# ArduinoInterface_v4_2.net
KiCad netlist of a schematic drawn in EAGLE
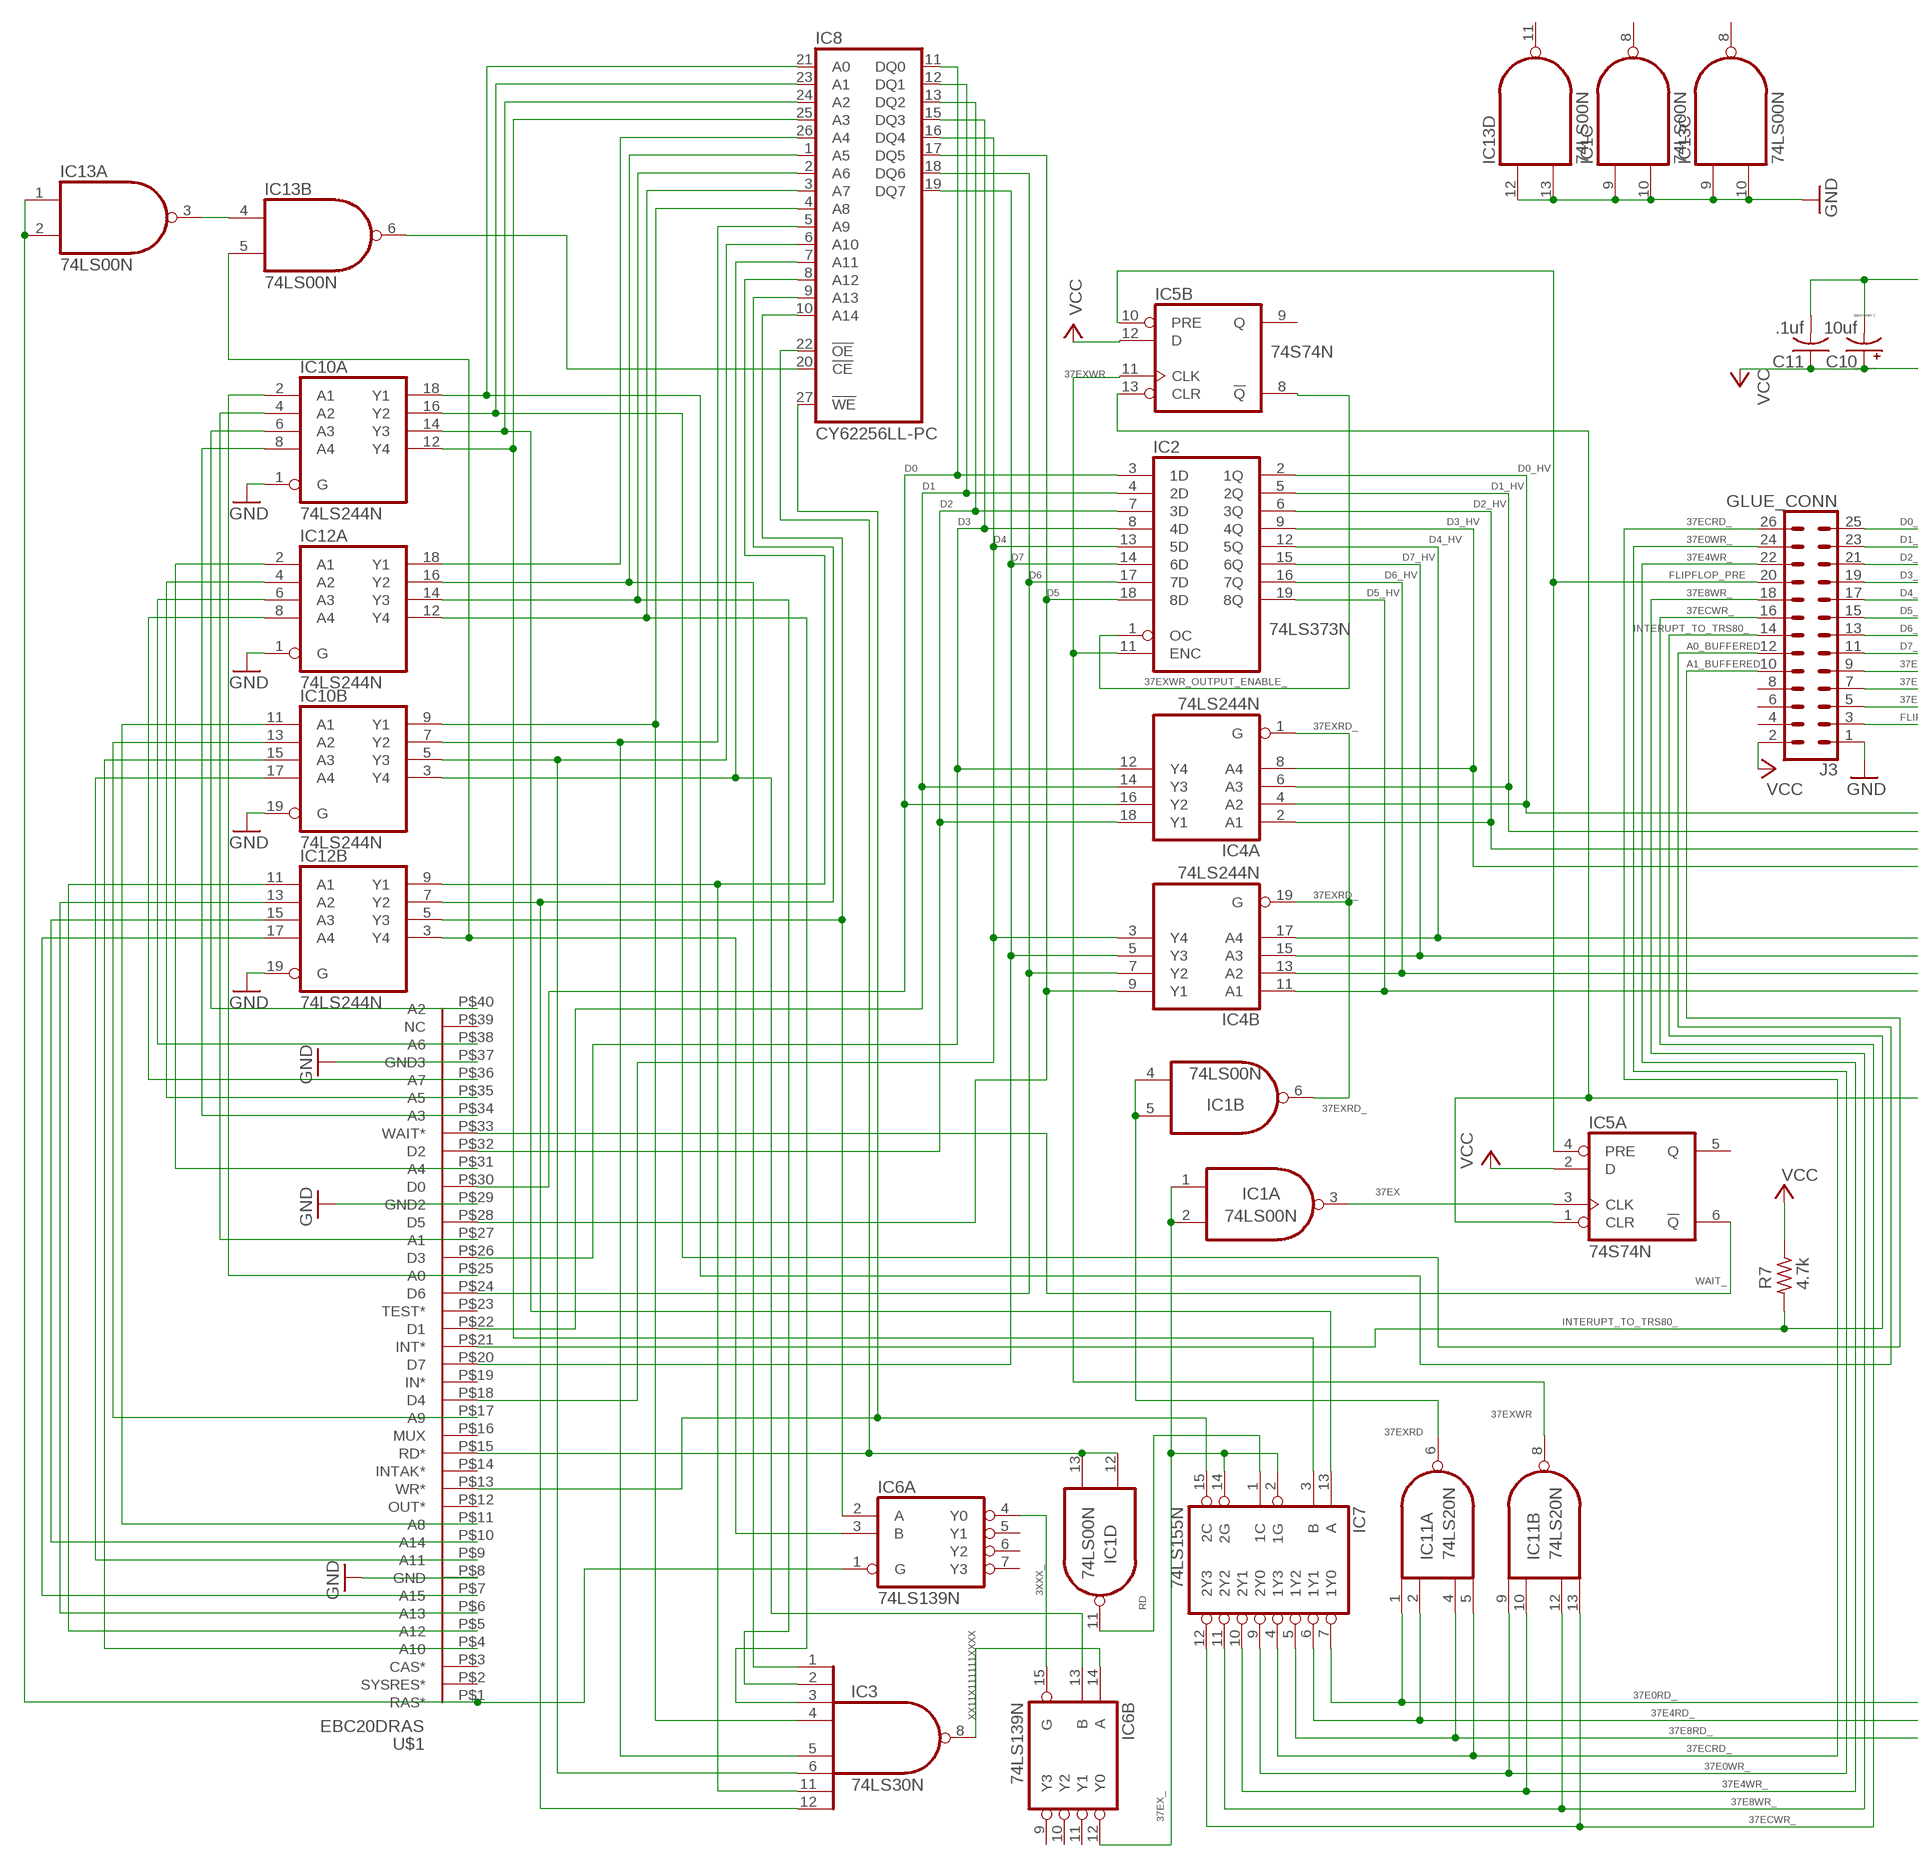
[diagram p0: schematic, sheet 1, part 1 of 2]
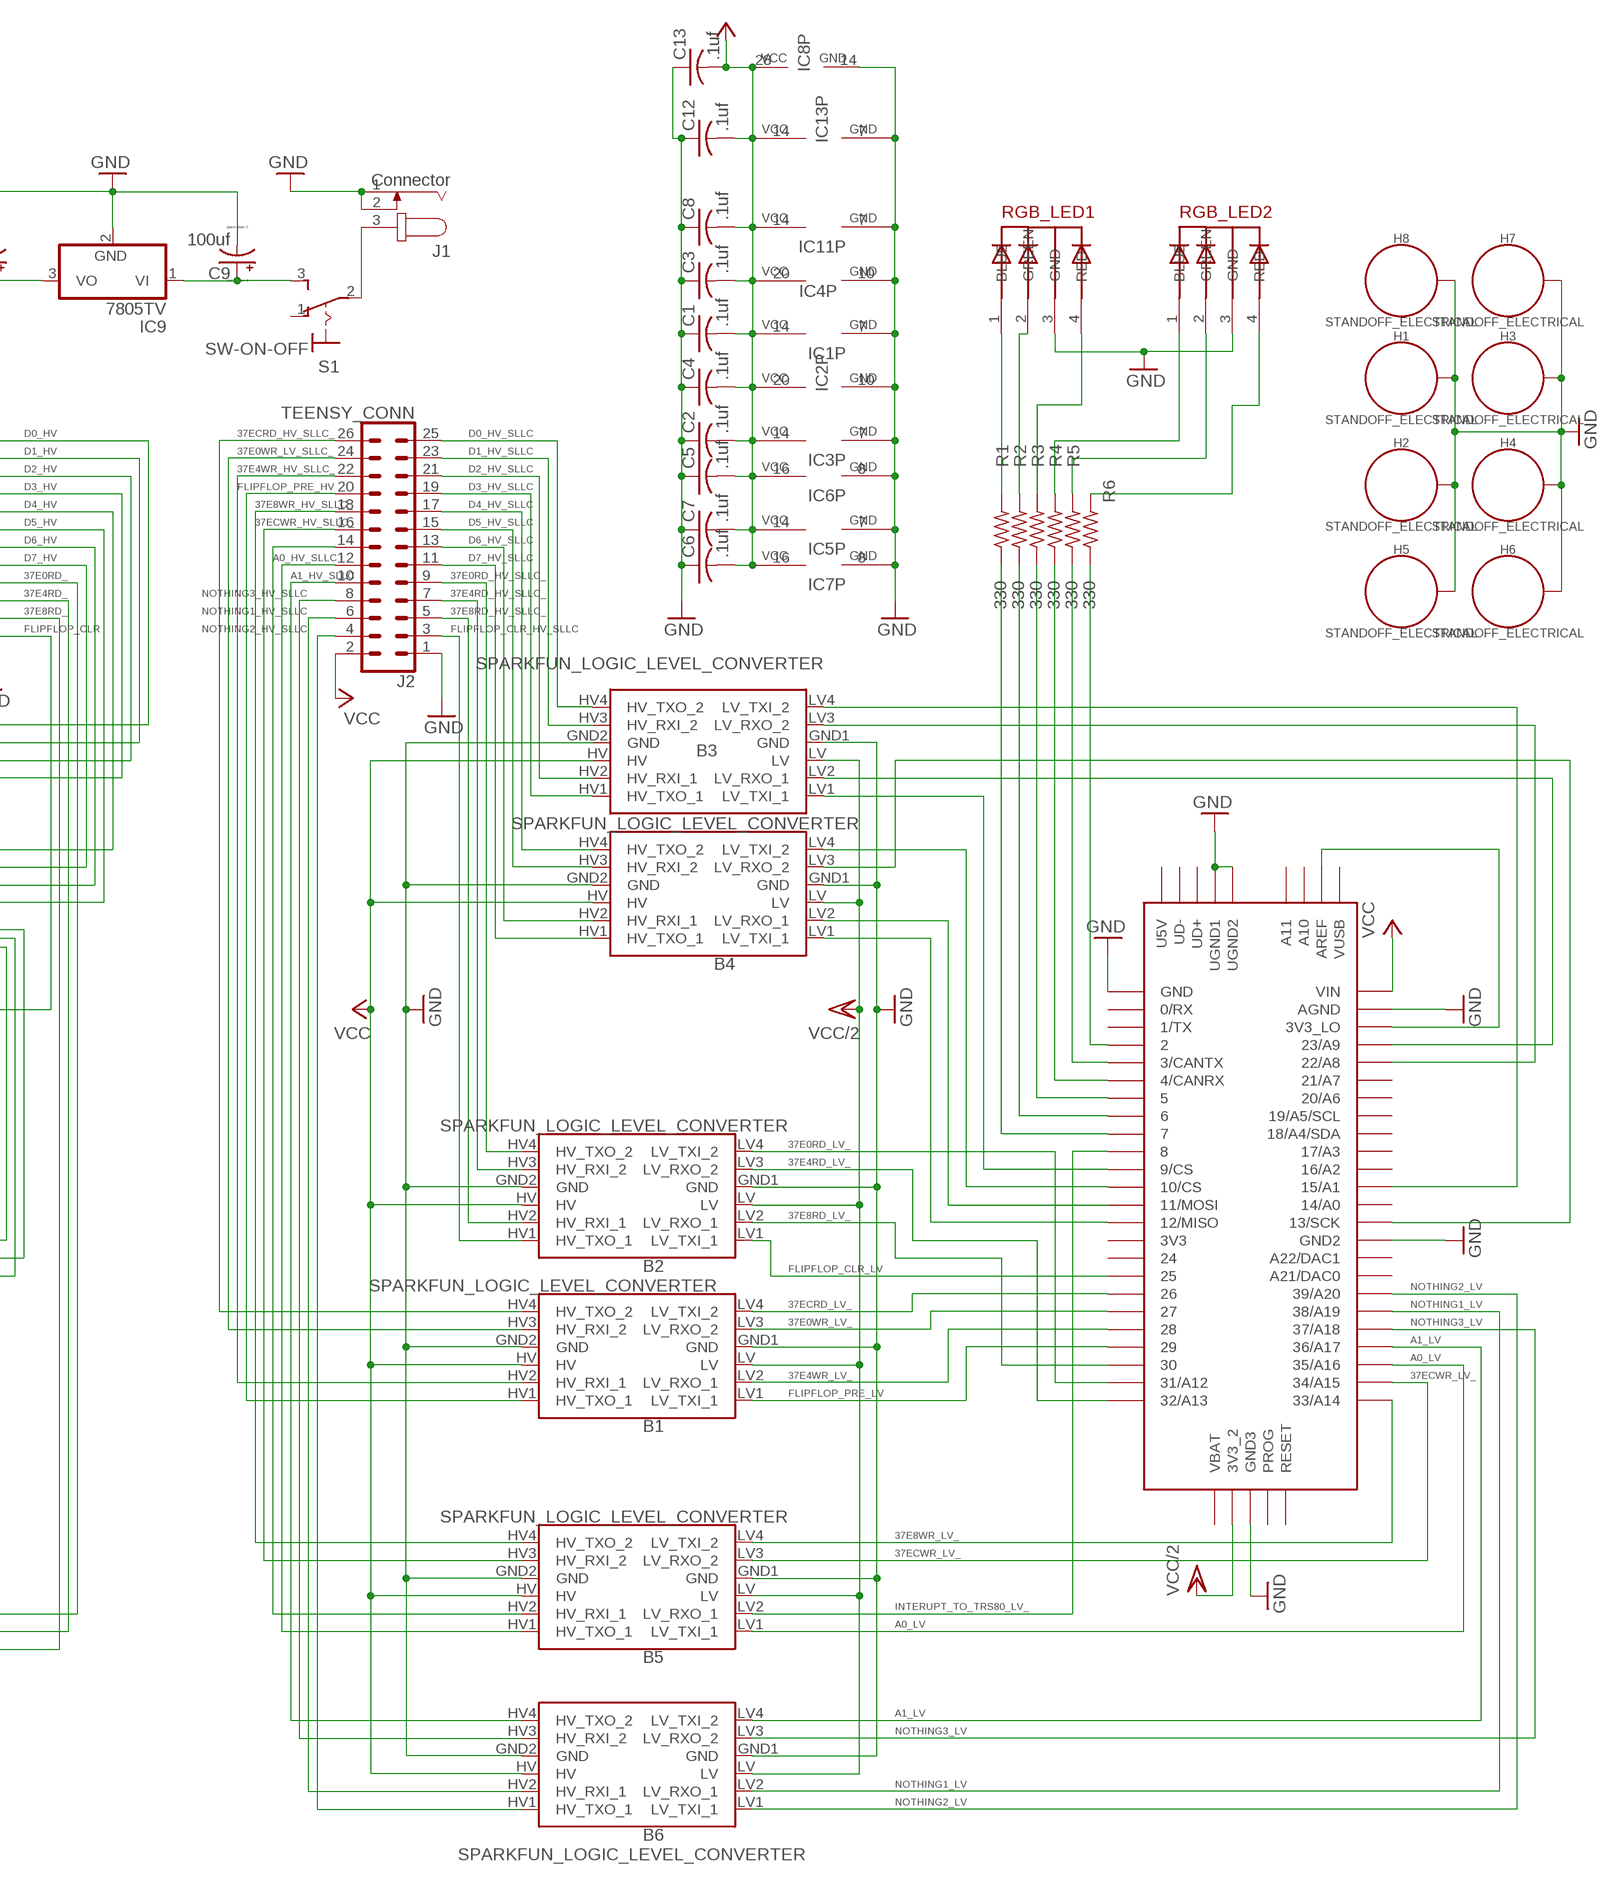
[diagram p1: schematic, sheet 1, part 2 of 2]

(export (version "E")
  (design (tool "Eeschema 10.0.6"))
  (components
    (comp (ref "B1")
      (value "SPARKFUN_LOGIC_LEVEL_CONVERTER")
      (footprint "eagle-import:SPARKFUN_LOGIC_LEVEL_CONVERTER")
      (libsource (lib "eagle-import") (part "SPARKFUN_LOGIC_LEVEL_CONVERTER"))
    )
    (comp (ref "B2")
      (value "SPARKFUN_LOGIC_LEVEL_CONVERTER")
      (footprint "eagle-import:SPARKFUN_LOGIC_LEVEL_CONVERTER")
      (libsource (lib "eagle-import") (part "SPARKFUN_LOGIC_LEVEL_CONVERTER"))
    )
    (comp (ref "B3")
      (value "SPARKFUN_LOGIC_LEVEL_CONVERTER")
      (footprint "eagle-import:SPARKFUN_LOGIC_LEVEL_CONVERTER")
      (libsource (lib "eagle-import") (part "SPARKFUN_LOGIC_LEVEL_CONVERTER"))
    )
    (comp (ref "B4")
      (value "SPARKFUN_LOGIC_LEVEL_CONVERTER")
      (footprint "eagle-import:SPARKFUN_LOGIC_LEVEL_CONVERTER")
      (libsource (lib "eagle-import") (part "SPARKFUN_LOGIC_LEVEL_CONVERTER"))
    )
    (comp (ref "B5")
      (value "SPARKFUN_LOGIC_LEVEL_CONVERTER")
      (footprint "eagle-import:SPARKFUN_LOGIC_LEVEL_CONVERTER")
      (libsource (lib "eagle-import") (part "SPARKFUN_LOGIC_LEVEL_CONVERTER"))
    )
    (comp (ref "B6")
      (value "SPARKFUN_LOGIC_LEVEL_CONVERTER")
      (footprint "eagle-import:SPARKFUN_LOGIC_LEVEL_CONVERTER")
      (libsource (lib "eagle-import") (part "SPARKFUN_LOGIC_LEVEL_CONVERTER"))
    )
    (comp (ref "C1")
      (value ".1uf")
      (footprint "eagle-import:C025-025X050")
      (libsource (lib "eagle-import") (part "C-US025-025X050"))
    )
    (comp (ref "C2")
      (value ".1uf")
      (footprint "eagle-import:C025-025X050")
      (libsource (lib "eagle-import") (part "C-US025-025X050"))
    )
    (comp (ref "C3")
      (value ".1uf")
      (footprint "eagle-import:C025-025X050")
      (libsource (lib "eagle-import") (part "C-US025-025X050"))
    )
    (comp (ref "C4")
      (value ".1uf")
      (footprint "eagle-import:C025-025X050")
      (libsource (lib "eagle-import") (part "C-US025-025X050"))
    )
    (comp (ref "C5")
      (value ".1uf")
      (footprint "eagle-import:C025-025X050")
      (libsource (lib "eagle-import") (part "C-US025-025X050"))
    )
    (comp (ref "C6")
      (value ".1uf")
      (footprint "eagle-import:C025-025X050")
      (libsource (lib "eagle-import") (part "C-US025-025X050"))
    )
    (comp (ref "C7")
      (value ".1uf")
      (footprint "eagle-import:C025-025X050")
      (libsource (lib "eagle-import") (part "C-US025-025X050"))
    )
    (comp (ref "C8")
      (value ".1uf")
      (footprint "eagle-import:C025-025X050")
      (libsource (lib "eagle-import") (part "C-US025-025X050"))
    )
    (comp (ref "C9")
      (value "100uf")
      (footprint "eagle-import:E5-6")
      (libsource (lib "eagle-import") (part "CPOL-USE5-6"))
    )
    (comp (ref "C10")
      (value "10uf")
      (footprint "eagle-import:E5-6")
      (libsource (lib "eagle-import") (part "CPOL-USE5-6"))
    )
    (comp (ref "C11")
      (value ".1uf")
      (footprint "eagle-import:C025-025X050")
      (libsource (lib "eagle-import") (part "C-US025-025X050"))
    )
    (comp (ref "C12")
      (value ".1uf")
      (footprint "eagle-import:C025-025X050")
      (libsource (lib "eagle-import") (part "C-US025-025X050"))
    )
    (comp (ref "C13")
      (value ".1uf")
      (footprint "eagle-import:C025-025X050")
      (libsource (lib "eagle-import") (part "C-US025-025X050"))
    )
    (comp (ref "H1")
      (value "STANDOFF_ELECTRICAL")
      (footprint "eagle-import:STANDOFF-ELECTRICAL")
      (libsource (lib "eagle-import") (part "STANDOFF_ELECTRICAL"))
    )
    (comp (ref "H2")
      (value "STANDOFF_ELECTRICAL")
      (footprint "eagle-import:STANDOFF-ELECTRICAL")
      (libsource (lib "eagle-import") (part "STANDOFF_ELECTRICAL"))
    )
    (comp (ref "H3")
      (value "STANDOFF_ELECTRICAL")
      (footprint "eagle-import:STANDOFF-ELECTRICAL")
      (libsource (lib "eagle-import") (part "STANDOFF_ELECTRICAL"))
    )
    (comp (ref "H4")
      (value "STANDOFF_ELECTRICAL")
      (footprint "eagle-import:STANDOFF-ELECTRICAL")
      (libsource (lib "eagle-import") (part "STANDOFF_ELECTRICAL"))
    )
    (comp (ref "H5")
      (value "STANDOFF_ELECTRICAL")
      (footprint "eagle-import:STANDOFF-ELECTRICAL")
      (libsource (lib "eagle-import") (part "STANDOFF_ELECTRICAL"))
    )
    (comp (ref "H6")
      (value "STANDOFF_ELECTRICAL")
      (footprint "eagle-import:STANDOFF-ELECTRICAL")
      (libsource (lib "eagle-import") (part "STANDOFF_ELECTRICAL"))
    )
    (comp (ref "H7")
      (value "STANDOFF_ELECTRICAL")
      (footprint "eagle-import:STANDOFF-ELECTRICAL")
      (libsource (lib "eagle-import") (part "STANDOFF_ELECTRICAL"))
    )
    (comp (ref "H8")
      (value "STANDOFF_ELECTRICAL")
      (footprint "eagle-import:STANDOFF-ELECTRICAL")
      (libsource (lib "eagle-import") (part "STANDOFF_ELECTRICAL"))
    )
    (comp (ref "IC1")
      (value "74LS00N")
      (footprint "eagle-import:DIL14")
      (libsource (lib "eagle-import") (part "7400NLS"))
    )
    (comp (ref "IC2")
      (value "74LS373N")
      (footprint "eagle-import:DIL20")
      (libsource (lib "eagle-import") (part "74373NLS"))
    )
    (comp (ref "IC3")
      (value "74LS30N")
      (footprint "eagle-import:DIL14")
      (libsource (lib "eagle-import") (part "7430NLS"))
    )
    (comp (ref "IC4")
      (value "74LS244N")
      (footprint "eagle-import:DIL20")
      (libsource (lib "eagle-import") (part "74244NLS"))
    )
    (comp (ref "IC5")
      (value "74S74N")
      (footprint "eagle-import:DIL14")
      (libsource (lib "eagle-import") (part "7474NS"))
    )
    (comp (ref "IC6")
      (value "74LS139N")
      (footprint "eagle-import:DIL16")
      (libsource (lib "eagle-import") (part "74139NLS"))
    )
    (comp (ref "IC7")
      (value "74LS155N")
      (footprint "eagle-import:DIL16")
      (libsource (lib "eagle-import") (part "74155NLS"))
    )
    (comp (ref "IC8")
      (value "CY62256LL-PC")
      (footprint "eagle-import:DIL28-6")
      (libsource (lib "eagle-import") (part "CY62256LL-?PC"))
    )
    (comp (ref "IC9")
      (value "7805TV")
      (footprint "eagle-import:TO220V")
      (libsource (lib "eagle-import") (part "78TV05"))
    )
    (comp (ref "IC10")
      (value "74LS244N")
      (footprint "eagle-import:DIL20")
      (libsource (lib "eagle-import") (part "74244NLS"))
    )
    (comp (ref "IC11")
      (value "74LS20N")
      (footprint "eagle-import:DIL14")
      (libsource (lib "eagle-import") (part "7420NLS"))
    )
    (comp (ref "IC12")
      (value "74LS244N")
      (footprint "eagle-import:DIL20")
      (libsource (lib "eagle-import") (part "74244NLS"))
    )
    (comp (ref "IC13")
      (value "74LS00N")
      (footprint "eagle-import:DIL14")
      (libsource (lib "eagle-import") (part "7400NLS"))
    )
    (comp (ref "J1")
      (value "Connector")
      (footprint "eagle-import:SPC4077")
      (libsource (lib "eagle-import") (part "JACK-PLUG0"))
    )
    (comp (ref "J2")
      (value "TEENSY_CONN")
      (footprint "eagle-import:2X13")
      (libsource (lib "eagle-import") (part "CONN_13X22X13"))
    )
    (comp (ref "J3")
      (value "GLUE_CONN")
      (footprint "eagle-import:2X13")
      (libsource (lib "eagle-import") (part "CONN_13X22X13"))
    )
    (comp (ref "R1")
      (value "330")
      (footprint "eagle-import:0204V")
      (libsource (lib "eagle-import") (part "R-US_0204/2V"))
    )
    (comp (ref "R2")
      (value "330")
      (footprint "eagle-import:0204V")
      (libsource (lib "eagle-import") (part "R-US_0204/2V"))
    )
    (comp (ref "R3")
      (value "330")
      (footprint "eagle-import:0204V")
      (libsource (lib "eagle-import") (part "R-US_0204/2V"))
    )
    (comp (ref "R4")
      (value "330")
      (footprint "eagle-import:0204V")
      (libsource (lib "eagle-import") (part "R-US_0204/2V"))
    )
    (comp (ref "R5")
      (value "330")
      (footprint "eagle-import:0204V")
      (libsource (lib "eagle-import") (part "R-US_0204/2V"))
    )
    (comp (ref "R6")
      (value "330")
      (footprint "eagle-import:0204V")
      (libsource (lib "eagle-import") (part "R-US_0204/2V"))
    )
    (comp (ref "R7")
      (value "4.7k")
      (footprint "eagle-import:0204V")
      (libsource (lib "eagle-import") (part "R-US_0204/2V"))
    )
    (comp (ref "RGB_LED1")
      (value "5MMRGBLED")
      (footprint "eagle-import:LED5MMRGB")
      (libsource (lib "eagle-import") (part "5MMRGBLED"))
    )
    (comp (ref "RGB_LED2")
      (value "5MMRGBLED")
      (footprint "eagle-import:LED5MMRGB")
      (libsource (lib "eagle-import") (part "5MMRGBLED"))
    )
    (comp (ref "S1")
      (value "SW-ON-OFF")
      (footprint "eagle-import:M9040P")
      (libsource (lib "eagle-import") (part "M9040P"))
    )
    (comp (ref "U$1")
      (value "EBC20DRAS")
      (footprint "eagle-import:EBC20DRAS")
      (libsource (lib "eagle-import") (part "EBC20DRAS"))
    )
    (comp (ref "U$2")
      (value "TEENSY_3.5/3.6")
      (footprint "eagle-import:TEENSY_3.5_3.6")
      (libsource (lib "eagle-import") (part "TEENSY_3.5/3.6"))
    )
  )
  (nets
    (net (code "1") (name "/3XXX_") (class "Default")
      (node (ref "IC6") (pin "15") (pinfunction "G_15") (pintype "input"))
      (node (ref "IC6") (pin "4") (pinfunction "Y0_4") (pintype "output"))
    )
    (net (code "2") (name "/37E0RD_") (class "Default")
      (node (ref "IC11") (pin "1") (pinfunction "I0_1") (pintype "input"))
      (node (ref "IC7") (pin "7") (pinfunction "1Y0_7") (pintype "output"))
      (node (ref "J3") (pin "9") (pinfunction "9_9") (pintype "passive"))
    )
    (net (code "3") (name "/37E0RD_HV_SLLC_") (class "Default")
      (node (ref "B2") (pin "HV4") (pinfunction "HV_TXO_2_HV4") (pintype "bidirectional"))
      (node (ref "J2") (pin "9") (pinfunction "9_9") (pintype "passive"))
    )
    (net (code "4") (name "/37E0RD_LV_") (class "Default")
      (node (ref "B2") (pin "LV4") (pinfunction "LV_TXI_2_LV4") (pintype "bidirectional"))
      (node (ref "U$2") (pin "31/A12") (pinfunction "31/A12_31/A12") (pintype "bidirectional"))
    )
    (net (code "5") (name "/37E0WR_") (class "Default")
      (node (ref "IC11") (pin "9") (pinfunction "I0_9") (pintype "input"))
      (node (ref "IC7") (pin "9") (pinfunction "2Y0_9") (pintype "output"))
      (node (ref "J3") (pin "24") (pinfunction "24_24") (pintype "passive"))
    )
    (net (code "6") (name "/37E0WR_LV_") (class "Default")
      (node (ref "B1") (pin "LV3") (pinfunction "LV_RXO_2_LV3") (pintype "bidirectional"))
      (node (ref "U$2") (pin "27") (pinfunction "27_27") (pintype "bidirectional"))
    )
    (net (code "7") (name "/37E0WR_LV_SLLC_") (class "Default")
      (node (ref "B1") (pin "HV3") (pinfunction "HV_RXI_2_HV3") (pintype "bidirectional"))
      (node (ref "J2") (pin "24") (pinfunction "24_24") (pintype "passive"))
    )
    (net (code "8") (name "/37E4RD_") (class "Default")
      (node (ref "IC11") (pin "2") (pinfunction "I1_2") (pintype "input"))
      (node (ref "IC7") (pin "6") (pinfunction "1Y1_6") (pintype "output"))
      (node (ref "J3") (pin "7") (pinfunction "7_7") (pintype "passive"))
    )
    (net (code "9") (name "/37E4RD_HV_SLLC_") (class "Default")
      (node (ref "B2") (pin "HV3") (pinfunction "HV_RXI_2_HV3") (pintype "bidirectional"))
      (node (ref "J2") (pin "7") (pinfunction "7_7") (pintype "passive"))
    )
    (net (code "10") (name "/37E4RD_LV_") (class "Default")
      (node (ref "B2") (pin "LV3") (pinfunction "LV_RXO_2_LV3") (pintype "bidirectional"))
      (node (ref "U$2") (pin "32/A13") (pinfunction "32/A13_32/A13") (pintype "bidirectional"))
    )
    (net (code "11") (name "/37E4WR_") (class "Default")
      (node (ref "IC11") (pin "10") (pinfunction "I1_10") (pintype "input"))
      (node (ref "IC7") (pin "10") (pinfunction "2Y1_10") (pintype "output"))
      (node (ref "J3") (pin "22") (pinfunction "22_22") (pintype "passive"))
    )
    (net (code "12") (name "/37E4WR_HV_SLLC_") (class "Default")
      (node (ref "B1") (pin "HV2") (pinfunction "HV_RXI_1_HV2") (pintype "bidirectional"))
      (node (ref "J2") (pin "22") (pinfunction "22_22") (pintype "passive"))
    )
    (net (code "13") (name "/37E4WR_LV_") (class "Default")
      (node (ref "B1") (pin "LV2") (pinfunction "LV_RXO_1_LV2") (pintype "bidirectional"))
      (node (ref "U$2") (pin "28") (pinfunction "28_28") (pintype "bidirectional"))
    )
    (net (code "14") (name "/37E8RD_") (class "Default")
      (node (ref "IC11") (pin "4") (pinfunction "I2_4") (pintype "input"))
      (node (ref "IC7") (pin "5") (pinfunction "1Y2_5") (pintype "output"))
      (node (ref "J3") (pin "5") (pinfunction "5_5") (pintype "passive"))
    )
    (net (code "15") (name "/37E8RD_HV_SLLC_") (class "Default")
      (node (ref "B2") (pin "HV2") (pinfunction "HV_RXI_1_HV2") (pintype "bidirectional"))
      (node (ref "J2") (pin "5") (pinfunction "5_5") (pintype "passive"))
    )
    (net (code "16") (name "/37E8RD_LV_") (class "Default")
      (node (ref "B2") (pin "LV2") (pinfunction "LV_RXO_1_LV2") (pintype "bidirectional"))
      (node (ref "U$2") (pin "30") (pinfunction "30_30") (pintype "bidirectional"))
    )
    (net (code "17") (name "/37E8WR_") (class "Default")
      (node (ref "IC11") (pin "12") (pinfunction "I2_12") (pintype "input"))
      (node (ref "IC7") (pin "11") (pinfunction "2Y2_11") (pintype "output"))
      (node (ref "J3") (pin "18") (pinfunction "18_18") (pintype "passive"))
    )
    (net (code "18") (name "/37E8WR_HV_SLLC_") (class "Default")
      (node (ref "B5") (pin "HV4") (pinfunction "HV_TXO_2_HV4") (pintype "bidirectional"))
      (node (ref "J2") (pin "18") (pinfunction "18_18") (pintype "passive"))
    )
    (net (code "19") (name "/37E8WR_LV_") (class "Default")
      (node (ref "B5") (pin "LV4") (pinfunction "LV_TXI_2_LV4") (pintype "bidirectional"))
      (node (ref "U$2") (pin "33/A14") (pinfunction "33/A14_33/A14") (pintype "bidirectional"))
    )
    (net (code "20") (name "/37ECRD_") (class "Default")
      (node (ref "IC11") (pin "5") (pinfunction "I3_5") (pintype "input"))
      (node (ref "IC7") (pin "4") (pinfunction "1Y3_4") (pintype "output"))
      (node (ref "J3") (pin "26") (pinfunction "26_26") (pintype "passive"))
    )
    (net (code "21") (name "/37ECRD_HV_SLLC_") (class "Default")
      (node (ref "B1") (pin "HV4") (pinfunction "HV_TXO_2_HV4") (pintype "bidirectional"))
      (node (ref "J2") (pin "26") (pinfunction "26_26") (pintype "passive"))
    )
    (net (code "22") (name "/37ECRD_LV_") (class "Default")
      (node (ref "B1") (pin "LV4") (pinfunction "LV_TXI_2_LV4") (pintype "bidirectional"))
      (node (ref "U$2") (pin "26") (pinfunction "26_26") (pintype "bidirectional"))
    )
    (net (code "23") (name "/37ECWR_") (class "Default")
      (node (ref "IC11") (pin "13") (pinfunction "I3_13") (pintype "input"))
      (node (ref "IC7") (pin "12") (pinfunction "2Y3_12") (pintype "output"))
      (node (ref "J3") (pin "16") (pinfunction "16_16") (pintype "passive"))
    )
    (net (code "24") (name "/37ECWR_HV_SLLC_") (class "Default")
      (node (ref "B5") (pin "HV3") (pinfunction "HV_RXI_2_HV3") (pintype "bidirectional"))
      (node (ref "J2") (pin "16") (pinfunction "16_16") (pintype "passive"))
    )
    (net (code "25") (name "/37ECWR_LV_") (class "Default")
      (node (ref "B5") (pin "LV3") (pinfunction "LV_RXO_2_LV3") (pintype "bidirectional"))
      (node (ref "U$2") (pin "34/A15") (pinfunction "34/A15_34/A15") (pintype "bidirectional"))
    )
    (net (code "26") (name "/37EX") (class "Default")
      (node (ref "IC1") (pin "3") (pinfunction "O_3") (pintype "output"))
      (node (ref "IC5") (pin "3") (pinfunction "CLK_3") (pintype "input"))
    )
    (net (code "27") (name "/37EXRD") (class "Default")
      (node (ref "IC1") (pin "4") (pinfunction "I0_4") (pintype "input"))
      (node (ref "IC1") (pin "5") (pinfunction "I1_5") (pintype "input"))
      (node (ref "IC11") (pin "6") (pinfunction "O_6") (pintype "output"))
    )
    (net (code "28") (name "/37EXRD_") (class "Default")
      (node (ref "IC1") (pin "6") (pinfunction "O_6") (pintype "output"))
      (node (ref "IC4") (pin "1") (pinfunction "G_1") (pintype "input"))
      (node (ref "IC4") (pin "19") (pinfunction "G_19") (pintype "input"))
    )
    (net (code "29") (name "/37EXWR") (class "Default")
      (node (ref "IC11") (pin "8") (pinfunction "O_8") (pintype "output"))
      (node (ref "IC2") (pin "11") (pinfunction "ENC_11") (pintype "input"))
      (node (ref "IC5") (pin "11") (pinfunction "CLK_11") (pintype "input"))
    )
    (net (code "30") (name "/37EXWR_OUTPUT_ENABLE_") (class "Default")
      (node (ref "IC2") (pin "1") (pinfunction "OC_1") (pintype "input"))
      (node (ref "IC5") (pin "8") (pinfunction "~{Q}_8") (pintype "output"))
    )
    (net (code "31") (name "/37EX_") (class "Default")
      (node (ref "IC1") (pin "1") (pinfunction "I0_1") (pintype "input"))
      (node (ref "IC1") (pin "2") (pinfunction "I1_2") (pintype "input"))
      (node (ref "IC6") (pin "12") (pinfunction "Y0_12") (pintype "output"))
      (node (ref "IC7") (pin "14") (pinfunction "2G_14") (pintype "input"))
      (node (ref "IC7") (pin "2") (pinfunction "1G_2") (pintype "input"))
    )
    (net (code "32") (name "/A0_BUFFERED") (class "Default")
      (node (ref "IC10") (pin "18") (pinfunction "Y1_18") (pintype "tri_state"))
      (node (ref "IC8") (pin "21") (pinfunction "A0_21") (pintype "input"))
      (node (ref "J3") (pin "12") (pinfunction "12_12") (pintype "passive"))
    )
    (net (code "33") (name "/A0_HV_SLLC") (class "Default")
      (node (ref "B5") (pin "HV1") (pinfunction "HV_TXO_1_HV1") (pintype "bidirectional"))
      (node (ref "J2") (pin "12") (pinfunction "12_12") (pintype "passive"))
    )
    (net (code "34") (name "/A0_LV") (class "Default")
      (node (ref "B5") (pin "LV1") (pinfunction "LV_TXI_1_LV1") (pintype "bidirectional"))
      (node (ref "U$2") (pin "35/A16") (pinfunction "35/A16_35/A16") (pintype "bidirectional"))
    )
    (net (code "35") (name "/A1_BUFFERED") (class "Default")
      (node (ref "IC10") (pin "16") (pinfunction "Y2_16") (pintype "tri_state"))
      (node (ref "IC8") (pin "23") (pinfunction "A1_23") (pintype "input"))
      (node (ref "J3") (pin "10") (pinfunction "10_10") (pintype "passive"))
    )
    (net (code "36") (name "/A1_HV_SLLC") (class "Default")
      (node (ref "B6") (pin "HV4") (pinfunction "HV_TXO_2_HV4") (pintype "bidirectional"))
      (node (ref "J2") (pin "10") (pinfunction "10_10") (pintype "passive"))
    )
    (net (code "37") (name "/A1_LV") (class "Default")
      (node (ref "B6") (pin "LV4") (pinfunction "LV_TXI_2_LV4") (pintype "bidirectional"))
      (node (ref "U$2") (pin "36/A17") (pinfunction "36/A17_36/A17") (pintype "bidirectional"))
    )
    (net (code "38") (name "/D0") (class "Default")
      (node (ref "IC2") (pin "3") (pinfunction "1D_3") (pintype "input"))
      (node (ref "IC4") (pin "16") (pinfunction "Y2_16") (pintype "tri_state"))
      (node (ref "IC8") (pin "11") (pinfunction "DQ0_11") (pintype "bidirectional"))
      (node (ref "U$1") (pin "P$30") (pinfunction "D0_P$30") (pintype "bidirectional"))
    )
    (net (code "39") (name "/D0_HV") (class "Default")
      (node (ref "IC2") (pin "2") (pinfunction "1Q_2") (pintype "tri_state"))
      (node (ref "IC4") (pin "4") (pinfunction "A2_4") (pintype "input"))
      (node (ref "J3") (pin "25") (pinfunction "25_25") (pintype "passive"))
    )
    (net (code "40") (name "/D0_HV_SLLC") (class "Default")
      (node (ref "B3") (pin "HV4") (pinfunction "HV_TXO_2_HV4") (pintype "bidirectional"))
      (node (ref "J2") (pin "25") (pinfunction "25_25") (pintype "passive"))
    )
    (net (code "41") (name "/D1") (class "Default")
      (node (ref "IC2") (pin "4") (pinfunction "2D_4") (pintype "input"))
      (node (ref "IC4") (pin "14") (pinfunction "Y3_14") (pintype "tri_state"))
      (node (ref "IC8") (pin "12") (pinfunction "DQ1_12") (pintype "bidirectional"))
      (node (ref "U$1") (pin "P$22") (pinfunction "D1_P$22") (pintype "bidirectional"))
    )
    (net (code "42") (name "/D1_HV") (class "Default")
      (node (ref "IC2") (pin "5") (pinfunction "2Q_5") (pintype "tri_state"))
      (node (ref "IC4") (pin "6") (pinfunction "A3_6") (pintype "input"))
      (node (ref "J3") (pin "23") (pinfunction "23_23") (pintype "passive"))
    )
    (net (code "43") (name "/D1_HV_SLLC") (class "Default")
      (node (ref "B3") (pin "HV3") (pinfunction "HV_RXI_2_HV3") (pintype "bidirectional"))
      (node (ref "J2") (pin "23") (pinfunction "23_23") (pintype "passive"))
    )
    (net (code "44") (name "/D2") (class "Default")
      (node (ref "IC2") (pin "7") (pinfunction "3D_7") (pintype "input"))
      (node (ref "IC4") (pin "18") (pinfunction "Y1_18") (pintype "tri_state"))
      (node (ref "IC8") (pin "13") (pinfunction "DQ2_13") (pintype "bidirectional"))
      (node (ref "U$1") (pin "P$32") (pinfunction "D2_P$32") (pintype "bidirectional"))
    )
    (net (code "45") (name "/D2_HV") (class "Default")
      (node (ref "IC2") (pin "6") (pinfunction "3Q_6") (pintype "tri_state"))
      (node (ref "IC4") (pin "2") (pinfunction "A1_2") (pintype "input"))
      (node (ref "J3") (pin "21") (pinfunction "21_21") (pintype "passive"))
    )
    (net (code "46") (name "/D2_HV_SLLC") (class "Default")
      (node (ref "B3") (pin "HV2") (pinfunction "HV_RXI_1_HV2") (pintype "bidirectional"))
      (node (ref "J2") (pin "21") (pinfunction "21_21") (pintype "passive"))
    )
    (net (code "47") (name "/D3") (class "Default")
      (node (ref "IC2") (pin "8") (pinfunction "4D_8") (pintype "input"))
      (node (ref "IC4") (pin "12") (pinfunction "Y4_12") (pintype "tri_state"))
      (node (ref "IC8") (pin "15") (pinfunction "DQ3_15") (pintype "bidirectional"))
      (node (ref "U$1") (pin "P$26") (pinfunction "D3_P$26") (pintype "bidirectional"))
    )
    (net (code "48") (name "/D3_HV") (class "Default")
      (node (ref "IC2") (pin "9") (pinfunction "4Q_9") (pintype "tri_state"))
      (node (ref "IC4") (pin "8") (pinfunction "A4_8") (pintype "input"))
      (node (ref "J3") (pin "19") (pinfunction "19_19") (pintype "passive"))
    )
    (net (code "49") (name "/D3_HV_SLLC") (class "Default")
      (node (ref "B3") (pin "HV1") (pinfunction "HV_TXO_1_HV1") (pintype "bidirectional"))
      (node (ref "J2") (pin "19") (pinfunction "19_19") (pintype "passive"))
    )
    (net (code "50") (name "/D4") (class "Default")
      (node (ref "IC2") (pin "13") (pinfunction "5D_13") (pintype "input"))
      (node (ref "IC4") (pin "3") (pinfunction "Y4_3") (pintype "tri_state"))
      (node (ref "IC8") (pin "16") (pinfunction "DQ4_16") (pintype "bidirectional"))
      (node (ref "U$1") (pin "P$18") (pinfunction "D4_P$18") (pintype "bidirectional"))
    )
    (net (code "51") (name "/D4_HV") (class "Default")
      (node (ref "IC2") (pin "12") (pinfunction "5Q_12") (pintype "tri_state"))
      (node (ref "IC4") (pin "17") (pinfunction "A4_17") (pintype "input"))
      (node (ref "J3") (pin "17") (pinfunction "17_17") (pintype "passive"))
    )
    (net (code "52") (name "/D4_HV_SLLC") (class "Default")
      (node (ref "B4") (pin "HV4") (pinfunction "HV_TXO_2_HV4") (pintype "bidirectional"))
      (node (ref "J2") (pin "17") (pinfunction "17_17") (pintype "passive"))
    )
    (net (code "53") (name "/D5") (class "Default")
      (node (ref "IC2") (pin "18") (pinfunction "8D_18") (pintype "input"))
      (node (ref "IC4") (pin "9") (pinfunction "Y1_9") (pintype "tri_state"))
      (node (ref "IC8") (pin "17") (pinfunction "DQ5_17") (pintype "bidirectional"))
      (node (ref "U$1") (pin "P$28") (pinfunction "D5_P$28") (pintype "bidirectional"))
    )
    (net (code "54") (name "/D5_HV") (class "Default")
      (node (ref "IC2") (pin "19") (pinfunction "8Q_19") (pintype "tri_state"))
      (node (ref "IC4") (pin "11") (pinfunction "A1_11") (pintype "input"))
      (node (ref "J3") (pin "15") (pinfunction "15_15") (pintype "passive"))
    )
    (net (code "55") (name "/D5_HV_SLLC") (class "Default")
      (node (ref "B4") (pin "HV3") (pinfunction "HV_RXI_2_HV3") (pintype "bidirectional"))
      (node (ref "J2") (pin "15") (pinfunction "15_15") (pintype "passive"))
    )
    (net (code "56") (name "/D6") (class "Default")
      (node (ref "IC2") (pin "17") (pinfunction "7D_17") (pintype "input"))
      (node (ref "IC4") (pin "7") (pinfunction "Y2_7") (pintype "tri_state"))
      (node (ref "IC8") (pin "18") (pinfunction "DQ6_18") (pintype "bidirectional"))
      (node (ref "U$1") (pin "P$24") (pinfunction "D6_P$24") (pintype "bidirectional"))
    )
    (net (code "57") (name "/D6_HV") (class "Default")
      (node (ref "IC2") (pin "16") (pinfunction "7Q_16") (pintype "tri_state"))
      (node (ref "IC4") (pin "13") (pinfunction "A2_13") (pintype "input"))
      (node (ref "J3") (pin "13") (pinfunction "13_13") (pintype "passive"))
    )
    (net (code "58") (name "/D6_HV_SLLC") (class "Default")
      (node (ref "B4") (pin "HV2") (pinfunction "HV_RXI_1_HV2") (pintype "bidirectional"))
      (node (ref "J2") (pin "13") (pinfunction "13_13") (pintype "passive"))
    )
    (net (code "59") (name "/D7") (class "Default")
      (node (ref "IC2") (pin "14") (pinfunction "6D_14") (pintype "input"))
      (node (ref "IC4") (pin "5") (pinfunction "Y3_5") (pintype "tri_state"))
      (node (ref "IC8") (pin "19") (pinfunction "DQ7_19") (pintype "bidirectional"))
      (node (ref "U$1") (pin "P$20") (pinfunction "D7_P$20") (pintype "bidirectional"))
    )
    (net (code "60") (name "/D7_HV") (class "Default")
      (node (ref "IC2") (pin "15") (pinfunction "6Q_15") (pintype "tri_state"))
      (node (ref "IC4") (pin "15") (pinfunction "A3_15") (pintype "input"))
      (node (ref "J3") (pin "11") (pinfunction "11_11") (pintype "passive"))
    )
    (net (code "61") (name "/D7_HV_SLLC") (class "Default")
      (node (ref "B4") (pin "HV1") (pinfunction "HV_TXO_1_HV1") (pintype "bidirectional"))
      (node (ref "J2") (pin "11") (pinfunction "11_11") (pintype "passive"))
    )
    (net (code "62") (name "/FLIPFLOP_CLR") (class "Default")
      (node (ref "IC5") (pin "1") (pinfunction "CLR_1") (pintype "input"))
      (node (ref "IC5") (pin "13") (pinfunction "CLR_13") (pintype "input"))
      (node (ref "J3") (pin "3") (pinfunction "3_3") (pintype "passive"))
    )
    (net (code "63") (name "/FLIPFLOP_CLR_HV_SLLC") (class "Default")
      (node (ref "B2") (pin "HV1") (pinfunction "HV_TXO_1_HV1") (pintype "bidirectional"))
      (node (ref "J2") (pin "3") (pinfunction "3_3") (pintype "passive"))
    )
    (net (code "64") (name "/FLIPFLOP_CLR_LV") (class "Default")
      (node (ref "B2") (pin "LV1") (pinfunction "LV_TXI_1_LV1") (pintype "bidirectional"))
      (node (ref "U$2") (pin "25") (pinfunction "25_25") (pintype "bidirectional"))
    )
    (net (code "65") (name "/FLIPFLOP_PRE") (class "Default")
      (node (ref "IC5") (pin "10") (pinfunction "PRE_10") (pintype "input"))
      (node (ref "IC5") (pin "4") (pinfunction "PRE_4") (pintype "input"))
      (node (ref "J3") (pin "20") (pinfunction "20_20") (pintype "passive"))
    )
    (net (code "66") (name "/FLIPFLOP_PRE_HV") (class "Default")
      (node (ref "B1") (pin "HV1") (pinfunction "HV_TXO_1_HV1") (pintype "bidirectional"))
      (node (ref "J2") (pin "20") (pinfunction "20_20") (pintype "passive"))
    )
    (net (code "67") (name "/FLIPFLOP_PRE_LV") (class "Default")
      (node (ref "B1") (pin "LV1") (pinfunction "LV_TXI_1_LV1") (pintype "bidirectional"))
      (node (ref "U$2") (pin "29") (pinfunction "29_29") (pintype "bidirectional"))
    )
    (net (code "68") (name "/INTERUPT_TO_TRS80_") (class "Default")
      (node (ref "J3") (pin "14") (pinfunction "14_14") (pintype "passive"))
      (node (ref "R7") (pin "2") (pinfunction "2_2") (pintype "passive"))
      (node (ref "U$1") (pin "P$21") (pinfunction "INT*_P$21") (pintype "bidirectional"))
    )
    (net (code "69") (name "/INTERUPT_TO_TRS80_LV_") (class "Default")
      (node (ref "B5") (pin "LV2") (pinfunction "LV_RXO_1_LV2") (pintype "bidirectional"))
      (node (ref "U$2") (pin "8") (pinfunction "8_8") (pintype "bidirectional"))
    )
    (net (code "70") (name "/NOTHING1_HV_SLLC") (class "Default")
      (node (ref "B6") (pin "HV2") (pinfunction "HV_RXI_1_HV2") (pintype "bidirectional"))
      (node (ref "J2") (pin "6") (pinfunction "6_6") (pintype "passive"))
    )
    (net (code "71") (name "/NOTHING1_LV") (class "Default")
      (node (ref "B6") (pin "LV2") (pinfunction "LV_RXO_1_LV2") (pintype "bidirectional"))
      (node (ref "U$2") (pin "38/A19") (pinfunction "38/A19_38/A19") (pintype "bidirectional"))
    )
    (net (code "72") (name "/NOTHING2_HV_SLLC") (class "Default")
      (node (ref "B6") (pin "HV1") (pinfunction "HV_TXO_1_HV1") (pintype "bidirectional"))
      (node (ref "J2") (pin "4") (pinfunction "4_4") (pintype "passive"))
    )
    (net (code "73") (name "/NOTHING2_LV") (class "Default")
      (node (ref "B6") (pin "LV1") (pinfunction "LV_TXI_1_LV1") (pintype "bidirectional"))
      (node (ref "U$2") (pin "39/A20") (pinfunction "39/A20_39/A20") (pintype "bidirectional"))
    )
    (net (code "74") (name "/NOTHING3_HV_SLLC") (class "Default")
      (node (ref "B6") (pin "HV3") (pinfunction "HV_RXI_2_HV3") (pintype "bidirectional"))
      (node (ref "J2") (pin "8") (pinfunction "8_8") (pintype "passive"))
    )
    (net (code "75") (name "/NOTHING3_LV") (class "Default")
      (node (ref "B6") (pin "LV3") (pinfunction "LV_RXO_2_LV3") (pintype "bidirectional"))
      (node (ref "U$2") (pin "37/A18") (pinfunction "37/A18_37/A18") (pintype "bidirectional"))
    )
    (net (code "76") (name "/RD") (class "Default")
      (node (ref "IC1") (pin "11") (pinfunction "O_11") (pintype "output"))
      (node (ref "IC7") (pin "1") (pinfunction "1C_1") (pintype "input"))
    )
    (net (code "77") (name "/WAIT_") (class "Default")
      (node (ref "IC5") (pin "6") (pinfunction "~{Q}_6") (pintype "output"))
      (node (ref "U$1") (pin "P$33") (pinfunction "WAIT*_P$33") (pintype "bidirectional"))
    )
    (net (code "78") (name "/XX11X111111XXXX") (class "Default")
      (node (ref "IC3") (pin "8") (pinfunction "O_8") (pintype "output"))
      (node (ref "IC6") (pin "14") (pinfunction "A_14") (pintype "input"))
    )
    (net (code "79") (name "GND") (class "Default")
      (node (ref "B1") (pin "GND1") (pinfunction "GND_GND1") (pintype "power_in"))
      (node (ref "B1") (pin "GND2") (pinfunction "GND_GND2") (pintype "power_in"))
      (node (ref "B2") (pin "GND1") (pinfunction "GND_GND1") (pintype "power_in"))
      (node (ref "B2") (pin "GND2") (pinfunction "GND_GND2") (pintype "power_in"))
      (node (ref "B3") (pin "GND1") (pinfunction "GND_GND1") (pintype "power_in"))
      (node (ref "B3") (pin "GND2") (pinfunction "GND_GND2") (pintype "power_in"))
      (node (ref "B4") (pin "GND1") (pinfunction "GND_GND1") (pintype "power_in"))
      (node (ref "B4") (pin "GND2") (pinfunction "GND_GND2") (pintype "power_in"))
      (node (ref "B5") (pin "GND1") (pinfunction "GND_GND1") (pintype "power_in"))
      (node (ref "B5") (pin "GND2") (pinfunction "GND_GND2") (pintype "power_in"))
      (node (ref "B6") (pin "GND1") (pinfunction "GND_GND1") (pintype "power_in"))
      (node (ref "B6") (pin "GND2") (pinfunction "GND_GND2") (pintype "power_in"))
      (node (ref "C1") (pin "1") (pinfunction "1_1") (pintype "passive"))
      (node (ref "C10") (pin "-") (pinfunction "-_-") (pintype "passive"))
      (node (ref "C11") (pin "2") (pinfunction "2_2") (pintype "passive"))
      (node (ref "C12") (pin "1") (pinfunction "1_1") (pintype "passive"))
      (node (ref "C13") (pin "1") (pinfunction "1_1") (pintype "passive"))
      (node (ref "C2") (pin "1") (pinfunction "1_1") (pintype "passive"))
      (node (ref "C3") (pin "1") (pinfunction "1_1") (pintype "passive"))
      (node (ref "C4") (pin "1") (pinfunction "1_1") (pintype "passive"))
      (node (ref "C5") (pin "1") (pinfunction "1_1") (pintype "passive"))
      (node (ref "C6") (pin "1") (pinfunction "1_1") (pintype "passive"))
      (node (ref "C7") (pin "1") (pinfunction "1_1") (pintype "passive"))
      (node (ref "C8") (pin "1") (pinfunction "1_1") (pintype "passive"))
      (node (ref "C9") (pin "-") (pinfunction "-_-") (pintype "passive"))
      (node (ref "H1") (pin "P1") (pinfunction "P$1_P1") (pintype "bidirectional"))
      (node (ref "H2") (pin "P1") (pinfunction "P$1_P1") (pintype "bidirectional"))
      (node (ref "H3") (pin "P1") (pinfunction "P$1_P1") (pintype "bidirectional"))
      (node (ref "H4") (pin "P1") (pinfunction "P$1_P1") (pintype "bidirectional"))
      (node (ref "H5") (pin "P1") (pinfunction "P$1_P1") (pintype "bidirectional"))
      (node (ref "H6") (pin "P1") (pinfunction "P$1_P1") (pintype "bidirectional"))
      (node (ref "H7") (pin "P1") (pinfunction "P$1_P1") (pintype "bidirectional"))
      (node (ref "H8") (pin "P1") (pinfunction "P$1_P1") (pintype "bidirectional"))
      (node (ref "IC1") (pin "10") (pinfunction "I1_10") (pintype "input"))
      (node (ref "IC1") (pin "7") (pinfunction "GND_7") (pintype "power_in"))
      (node (ref "IC1") (pin "9") (pinfunction "I0_9") (pintype "input"))
      (node (ref "IC10") (pin "1") (pinfunction "G_1") (pintype "input"))
      (node (ref "IC10") (pin "19") (pinfunction "G_19") (pintype "input"))
      (node (ref "IC11") (pin "7") (pinfunction "GND_7") (pintype "power_in"))
      (node (ref "IC12") (pin "1") (pinfunction "G_1") (pintype "input"))
      (node (ref "IC12") (pin "19") (pinfunction "G_19") (pintype "input"))
      (node (ref "IC13") (pin "10") (pinfunction "I1_10") (pintype "input"))
      (node (ref "IC13") (pin "12") (pinfunction "I0_12") (pintype "input"))
      (node (ref "IC13") (pin "13") (pinfunction "I1_13") (pintype "input"))
      (node (ref "IC13") (pin "7") (pinfunction "GND_7") (pintype "power_in"))
      (node (ref "IC13") (pin "9") (pinfunction "I0_9") (pintype "input"))
      (node (ref "IC2") (pin "10") (pinfunction "GND_10") (pintype "power_in"))
      (node (ref "IC3") (pin "7") (pinfunction "GND_7") (pintype "power_in"))
      (node (ref "IC4") (pin "10") (pinfunction "GND_10") (pintype "power_in"))
      (node (ref "IC5") (pin "7") (pinfunction "GND_7") (pintype "power_in"))
      (node (ref "IC6") (pin "8") (pinfunction "GND_8") (pintype "power_in"))
      (node (ref "IC7") (pin "8") (pinfunction "GND_8") (pintype "power_in"))
      (node (ref "IC8") (pin "14") (pinfunction "GND_14") (pintype "power_in"))
      (node (ref "IC9") (pin "2") (pinfunction "GND_2") (pintype "passive"))
      (node (ref "J1") (pin "1") (pinfunction "1_1") (pintype "passive"))
      (node (ref "J1") (pin "2") (pinfunction "2_2") (pintype "passive"))
      (node (ref "J2") (pin "1") (pinfunction "1_1") (pintype "passive"))
      (node (ref "J3") (pin "1") (pinfunction "1_1") (pintype "passive"))
      (node (ref "RGB_LED1") (pin "3") (pinfunction "GND_3") (pintype "bidirectional"))
      (node (ref "RGB_LED2") (pin "3") (pinfunction "GND_3") (pintype "bidirectional"))
      (node (ref "U$1") (pin "P$29") (pinfunction "GND2_P$29") (pintype "bidirectional"))
      (node (ref "U$1") (pin "P$37") (pinfunction "GND3_P$37") (pintype "bidirectional"))
      (node (ref "U$1") (pin "P$8") (pinfunction "GND_P$8") (pintype "bidirectional"))
      (node (ref "U$2") (pin "AGND") (pinfunction "AGND_AGND") (pintype "bidirectional"))
      (node (ref "U$2") (pin "GND") (pinfunction "GND_GND") (pintype "bidirectional"))
      (node (ref "U$2") (pin "GND2") (pinfunction "GND2_GND2") (pintype "bidirectional"))
      (node (ref "U$2") (pin "GND3") (pinfunction "GND3_GND3") (pintype "bidirectional"))
      (node (ref "U$2") (pin "UGND1") (pinfunction "UGND1_UGND1") (pintype "bidirectional"))
      (node (ref "U$2") (pin "UGND2") (pinfunction "UGND2_UGND2") (pintype "bidirectional"))
    )
    (net (code "80") (name "Net-(B3-LV_RXO_1)") (class "Default")
      (node (ref "B3") (pin "LV2") (pinfunction "LV_RXO_1_LV2") (pintype "bidirectional"))
      (node (ref "U$2") (pin "23/A9") (pinfunction "23/A9_23/A9") (pintype "bidirectional"))
    )
    (net (code "81") (name "Net-(B3-LV_RXO_2)") (class "Default")
      (node (ref "B3") (pin "LV3") (pinfunction "LV_RXO_2_LV3") (pintype "bidirectional"))
      (node (ref "U$2") (pin "22/A8") (pinfunction "22/A8_22/A8") (pintype "bidirectional"))
    )
    (net (code "82") (name "Net-(B3-LV_TXI_1)") (class "Default")
      (node (ref "B3") (pin "LV1") (pinfunction "LV_TXI_1_LV1") (pintype "bidirectional"))
      (node (ref "U$2") (pin "9/CS") (pinfunction "9/CS_9/CS") (pintype "bidirectional"))
    )
    (net (code "83") (name "Net-(B3-LV_TXI_2)") (class "Default")
      (node (ref "B3") (pin "LV4") (pinfunction "LV_TXI_2_LV4") (pintype "bidirectional"))
      (node (ref "U$2") (pin "15/A1") (pinfunction "15/A1_15/A1") (pintype "bidirectional"))
    )
    (net (code "84") (name "Net-(B4-LV_RXO_1)") (class "Default")
      (node (ref "B4") (pin "LV2") (pinfunction "LV_RXO_1_LV2") (pintype "bidirectional"))
      (node (ref "U$2") (pin "11/MOSI") (pinfunction "11/MOSI_11/MOSI") (pintype "bidirectional"))
    )
    (net (code "85") (name "Net-(B4-LV_RXO_2)") (class "Default")
      (node (ref "B4") (pin "LV3") (pinfunction "LV_RXO_2_LV3") (pintype "bidirectional"))
      (node (ref "U$2") (pin "13/SCK") (pinfunction "13/SCK_13/SCK") (pintype "bidirectional"))
    )
    (net (code "86") (name "Net-(B4-LV_TXI_1)") (class "Default")
      (node (ref "B4") (pin "LV1") (pinfunction "LV_TXI_1_LV1") (pintype "bidirectional"))
      (node (ref "U$2") (pin "12/MISO") (pinfunction "12/MISO_12/MISO") (pintype "bidirectional"))
    )
    (net (code "87") (name "Net-(B4-LV_TXI_2)") (class "Default")
      (node (ref "B4") (pin "LV4") (pinfunction "LV_TXI_2_LV4") (pintype "bidirectional"))
      (node (ref "U$2") (pin "10/CS") (pinfunction "10/CS_10/CS") (pintype "bidirectional"))
    )
    (net (code "88") (name "Net-(B5-HV_RXI_1)") (class "Default")
      (node (ref "B5") (pin "HV2") (pinfunction "HV_RXI_1_HV2") (pintype "bidirectional"))
      (node (ref "J2") (pin "14") (pinfunction "14_14") (pintype "passive"))
    )
    (net (code "89") (name "Net-(IC1D-I0)") (class "Default")
      (node (ref "IC1") (pin "12") (pinfunction "I0_12") (pintype "input"))
      (node (ref "IC1") (pin "13") (pinfunction "I1_13") (pintype "input"))
      (node (ref "IC8") (pin "22") (pinfunction "~{OE}_22") (pintype "input"))
      (node (ref "U$1") (pin "P$15") (pinfunction "RD*_P$15") (pintype "bidirectional"))
    )
    (net (code "90") (name "Net-(IC7A-2C)") (class "Default")
      (node (ref "IC7") (pin "15") (pinfunction "2C_15") (pintype "input"))
      (node (ref "IC8") (pin "27") (pinfunction "~{WE}_27") (pintype "input"))
      (node (ref "U$1") (pin "P$13") (pinfunction "WR*_P$13") (pintype "bidirectional"))
    )
    (net (code "91") (name "Net-(IC9-VI)") (class "Default")
      (node (ref "C9") (pin "+") (pinfunction "+_+") (pintype "passive"))
      (node (ref "IC9") (pin "1") (pinfunction "VI_1") (pintype "input"))
      (node (ref "S1") (pin "3") (pinfunction "S_3") (pintype "passive"))
    )
    (net (code "92") (name "Net-(IC10A-A1)") (class "Default")
      (node (ref "IC10") (pin "2") (pinfunction "A1_2") (pintype "input"))
      (node (ref "U$1") (pin "P$25") (pinfunction "A0_P$25") (pintype "bidirectional"))
    )
    (net (code "93") (name "Net-(IC10A-A2)") (class "Default")
      (node (ref "IC10") (pin "4") (pinfunction "A2_4") (pintype "input"))
      (node (ref "U$1") (pin "P$27") (pinfunction "A1_P$27") (pintype "bidirectional"))
    )
    (net (code "94") (name "Net-(IC10A-A3)") (class "Default")
      (node (ref "IC10") (pin "6") (pinfunction "A3_6") (pintype "input"))
      (node (ref "U$1") (pin "P$40") (pinfunction "A2_P$40") (pintype "bidirectional"))
    )
    (net (code "95") (name "Net-(IC10A-A4)") (class "Default")
      (node (ref "IC10") (pin "8") (pinfunction "A4_8") (pintype "input"))
      (node (ref "U$1") (pin "P$34") (pinfunction "A3_P$34") (pintype "bidirectional"))
    )
    (net (code "96") (name "Net-(IC10A-Y3)") (class "Default")
      (node (ref "IC10") (pin "14") (pinfunction "Y3_14") (pintype "tri_state"))
      (node (ref "IC7") (pin "13") (pinfunction "A_13") (pintype "input"))
      (node (ref "IC8") (pin "24") (pinfunction "A2_24") (pintype "input"))
    )
    (net (code "97") (name "Net-(IC10A-Y4)") (class "Default")
      (node (ref "IC10") (pin "12") (pinfunction "Y4_12") (pintype "tri_state"))
      (node (ref "IC7") (pin "3") (pinfunction "B_3") (pintype "input"))
      (node (ref "IC8") (pin "25") (pinfunction "A3_25") (pintype "input"))
    )
    (net (code "98") (name "Net-(IC10B-A1)") (class "Default")
      (node (ref "IC10") (pin "11") (pinfunction "A1_11") (pintype "input"))
      (node (ref "U$1") (pin "P$11") (pinfunction "A8_P$11") (pintype "bidirectional"))
    )
    (net (code "99") (name "Net-(IC10B-A2)") (class "Default")
      (node (ref "IC10") (pin "13") (pinfunction "A2_13") (pintype "input"))
      (node (ref "U$1") (pin "P$17") (pinfunction "A9_P$17") (pintype "bidirectional"))
    )
    (net (code "100") (name "Net-(IC10B-A3)") (class "Default")
      (node (ref "IC10") (pin "15") (pinfunction "A3_15") (pintype "input"))
      (node (ref "U$1") (pin "P$4") (pinfunction "A10_P$4") (pintype "bidirectional"))
    )
    (net (code "101") (name "Net-(IC10B-A4)") (class "Default")
      (node (ref "IC10") (pin "17") (pinfunction "A4_17") (pintype "input"))
      (node (ref "U$1") (pin "P$9") (pinfunction "A11_P$9") (pintype "bidirectional"))
    )
    (net (code "102") (name "Net-(IC10B-Y1)") (class "Default")
      (node (ref "IC10") (pin "9") (pinfunction "Y1_9") (pintype "tri_state"))
      (node (ref "IC3") (pin "4") (pinfunction "I3_4") (pintype "input"))
      (node (ref "IC8") (pin "4") (pinfunction "A8_4") (pintype "input"))
    )
    (net (code "103") (name "Net-(IC10B-Y2)") (class "Default")
      (node (ref "IC10") (pin "7") (pinfunction "Y2_7") (pintype "tri_state"))
      (node (ref "IC3") (pin "5") (pinfunction "I4_5") (pintype "input"))
      (node (ref "IC8") (pin "5") (pinfunction "A9_5") (pintype "input"))
    )
    (net (code "104") (name "Net-(IC10B-Y3)") (class "Default")
      (node (ref "IC10") (pin "5") (pinfunction "Y3_5") (pintype "tri_state"))
      (node (ref "IC3") (pin "6") (pinfunction "I5_6") (pintype "input"))
      (node (ref "IC8") (pin "6") (pinfunction "A10_6") (pintype "input"))
    )
    (net (code "105") (name "Net-(IC10B-Y4)") (class "Default")
      (node (ref "IC10") (pin "3") (pinfunction "Y4_3") (pintype "tri_state"))
      (node (ref "IC6") (pin "13") (pinfunction "B_13") (pintype "input"))
      (node (ref "IC8") (pin "7") (pinfunction "A11_7") (pintype "input"))
    )
    (net (code "106") (name "Net-(IC12A-A1)") (class "Default")
      (node (ref "IC12") (pin "2") (pinfunction "A1_2") (pintype "input"))
      (node (ref "U$1") (pin "P$31") (pinfunction "A4_P$31") (pintype "bidirectional"))
    )
    (net (code "107") (name "Net-(IC12A-A2)") (class "Default")
      (node (ref "IC12") (pin "4") (pinfunction "A2_4") (pintype "input"))
      (node (ref "U$1") (pin "P$35") (pinfunction "A5_P$35") (pintype "bidirectional"))
    )
    (net (code "108") (name "Net-(IC12A-A3)") (class "Default")
      (node (ref "IC12") (pin "6") (pinfunction "A3_6") (pintype "input"))
      (node (ref "U$1") (pin "P$38") (pinfunction "A6_P$38") (pintype "bidirectional"))
    )
    (net (code "109") (name "Net-(IC12A-A4)") (class "Default")
      (node (ref "IC12") (pin "8") (pinfunction "A4_8") (pintype "input"))
      (node (ref "U$1") (pin "P$36") (pinfunction "A7_P$36") (pintype "bidirectional"))
    )
    (net (code "110") (name "Net-(IC12A-Y1)") (class "Default")
      (node (ref "IC12") (pin "18") (pinfunction "Y1_18") (pintype "tri_state"))
      (node (ref "IC8") (pin "26") (pinfunction "A4_26") (pintype "input"))
    )
    (net (code "111") (name "Net-(IC12A-Y2)") (class "Default")
      (node (ref "IC12") (pin "16") (pinfunction "Y2_16") (pintype "tri_state"))
      (node (ref "IC3") (pin "1") (pinfunction "I0_1") (pintype "input"))
      (node (ref "IC8") (pin "1") (pinfunction "A5_1") (pintype "input"))
    )
    (net (code "112") (name "Net-(IC12A-Y3)") (class "Default")
      (node (ref "IC12") (pin "14") (pinfunction "Y3_14") (pintype "tri_state"))
      (node (ref "IC3") (pin "2") (pinfunction "I1_2") (pintype "input"))
      (node (ref "IC8") (pin "2") (pinfunction "A6_2") (pintype "input"))
    )
    (net (code "113") (name "Net-(IC12A-Y4)") (class "Default")
      (node (ref "IC12") (pin "12") (pinfunction "Y4_12") (pintype "tri_state"))
      (node (ref "IC3") (pin "3") (pinfunction "I2_3") (pintype "input"))
      (node (ref "IC8") (pin "3") (pinfunction "A7_3") (pintype "input"))
    )
    (net (code "114") (name "Net-(IC12B-A1)") (class "Default")
      (node (ref "IC12") (pin "11") (pinfunction "A1_11") (pintype "input"))
      (node (ref "U$1") (pin "P$5") (pinfunction "A12_P$5") (pintype "bidirectional"))
    )
    (net (code "115") (name "Net-(IC12B-A2)") (class "Default")
      (node (ref "IC12") (pin "13") (pinfunction "A2_13") (pintype "input"))
      (node (ref "U$1") (pin "P$6") (pinfunction "A13_P$6") (pintype "bidirectional"))
    )
    (net (code "116") (name "Net-(IC12B-A3)") (class "Default")
      (node (ref "IC12") (pin "15") (pinfunction "A3_15") (pintype "input"))
      (node (ref "U$1") (pin "P$10") (pinfunction "A14_P$10") (pintype "bidirectional"))
    )
    (net (code "117") (name "Net-(IC12B-A4)") (class "Default")
      (node (ref "IC12") (pin "17") (pinfunction "A4_17") (pintype "input"))
      (node (ref "U$1") (pin "P$7") (pinfunction "A15_P$7") (pintype "bidirectional"))
    )
    (net (code "118") (name "Net-(IC12B-Y1)") (class "Default")
      (node (ref "IC12") (pin "9") (pinfunction "Y1_9") (pintype "tri_state"))
      (node (ref "IC3") (pin "11") (pinfunction "I6_11") (pintype "input"))
      (node (ref "IC8") (pin "8") (pinfunction "A12_8") (pintype "input"))
    )
    (net (code "119") (name "Net-(IC12B-Y2)") (class "Default")
      (node (ref "IC12") (pin "7") (pinfunction "Y2_7") (pintype "tri_state"))
      (node (ref "IC3") (pin "12") (pinfunction "I7_12") (pintype "input"))
      (node (ref "IC8") (pin "9") (pinfunction "A13_9") (pintype "input"))
    )
    (net (code "120") (name "Net-(IC12B-Y3)") (class "Default")
      (node (ref "IC12") (pin "5") (pinfunction "Y3_5") (pintype "tri_state"))
      (node (ref "IC6") (pin "2") (pinfunction "A_2") (pintype "input"))
      (node (ref "IC8") (pin "10") (pinfunction "A14_10") (pintype "input"))
    )
    (net (code "121") (name "Net-(IC12B-Y4)") (class "Default")
      (node (ref "IC12") (pin "3") (pinfunction "Y4_3") (pintype "tri_state"))
      (node (ref "IC13") (pin "5") (pinfunction "I1_5") (pintype "input"))
      (node (ref "IC6") (pin "3") (pinfunction "B_3") (pintype "input"))
    )
    (net (code "122") (name "Net-(IC13A-I0)") (class "Default")
      (node (ref "IC13") (pin "1") (pinfunction "I0_1") (pintype "input"))
      (node (ref "IC13") (pin "2") (pinfunction "I1_2") (pintype "input"))
      (node (ref "IC6") (pin "1") (pinfunction "G_1") (pintype "input"))
      (node (ref "U$1") (pin "P$1") (pinfunction "RAS*_P$1") (pintype "bidirectional"))
    )
    (net (code "123") (name "Net-(IC13A-O)") (class "Default")
      (node (ref "IC13") (pin "3") (pinfunction "O_3") (pintype "output"))
      (node (ref "IC13") (pin "4") (pinfunction "I0_4") (pintype "input"))
    )
    (net (code "124") (name "Net-(IC13B-O)") (class "Default")
      (node (ref "IC13") (pin "6") (pinfunction "O_6") (pintype "output"))
      (node (ref "IC8") (pin "20") (pinfunction "~{CE}_20") (pintype "input"))
    )
    (net (code "125") (name "Net-(R1-Pad1)") (class "Default")
      (node (ref "R1") (pin "1") (pinfunction "1_1") (pintype "passive"))
      (node (ref "U$2") (pin "7") (pinfunction "7_7") (pintype "bidirectional"))
    )
    (net (code "126") (name "Net-(R2-Pad1)") (class "Default")
      (node (ref "R2") (pin "1") (pinfunction "1_1") (pintype "passive"))
      (node (ref "U$2") (pin "6") (pinfunction "6_6") (pintype "bidirectional"))
    )
    (net (code "127") (name "Net-(R3-Pad1)") (class "Default")
      (node (ref "R3") (pin "1") (pinfunction "1_1") (pintype "passive"))
      (node (ref "U$2") (pin "5") (pinfunction "5_5") (pintype "bidirectional"))
    )
    (net (code "128") (name "Net-(R4-Pad1)") (class "Default")
      (node (ref "R4") (pin "1") (pinfunction "1_1") (pintype "passive"))
      (node (ref "U$2") (pin "4/CANRX") (pinfunction "4/CANRX_4/CANRX") (pintype "bidirectional"))
    )
    (net (code "129") (name "Net-(R5-Pad1)") (class "Default")
      (node (ref "R5") (pin "1") (pinfunction "1_1") (pintype "passive"))
      (node (ref "U$2") (pin "3/CANTX") (pinfunction "3/CANTX_3/CANTX") (pintype "bidirectional"))
    )
    (net (code "130") (name "Net-(R6-Pad1)") (class "Default")
      (node (ref "R6") (pin "1") (pinfunction "1_1") (pintype "passive"))
      (node (ref "U$2") (pin "2") (pinfunction "2_2") (pintype "bidirectional"))
    )
    (net (code "131") (name "Net-(RGB_LED1-BLUE)") (class "Default")
      (node (ref "R1") (pin "2") (pinfunction "2_2") (pintype "passive"))
      (node (ref "RGB_LED1") (pin "1") (pinfunction "BLUE_1") (pintype "bidirectional"))
    )
    (net (code "132") (name "Net-(RGB_LED1-GREEN)") (class "Default")
      (node (ref "R2") (pin "2") (pinfunction "2_2") (pintype "passive"))
      (node (ref "RGB_LED1") (pin "2") (pinfunction "GREEN_2") (pintype "bidirectional"))
    )
    (net (code "133") (name "Net-(RGB_LED1-RED)") (class "Default")
      (node (ref "R3") (pin "2") (pinfunction "2_2") (pintype "passive"))
      (node (ref "RGB_LED1") (pin "4") (pinfunction "RED_4") (pintype "bidirectional"))
    )
    (net (code "134") (name "Net-(RGB_LED2-BLUE)") (class "Default")
      (node (ref "R4") (pin "2") (pinfunction "2_2") (pintype "passive"))
      (node (ref "RGB_LED2") (pin "1") (pinfunction "BLUE_1") (pintype "bidirectional"))
    )
    (net (code "135") (name "Net-(RGB_LED2-GREEN)") (class "Default")
      (node (ref "R5") (pin "2") (pinfunction "2_2") (pintype "passive"))
      (node (ref "RGB_LED2") (pin "2") (pinfunction "GREEN_2") (pintype "bidirectional"))
    )
    (net (code "136") (name "Net-(RGB_LED2-RED)") (class "Default")
      (node (ref "R6") (pin "2") (pinfunction "2_2") (pintype "passive"))
      (node (ref "RGB_LED2") (pin "4") (pinfunction "RED_4") (pintype "bidirectional"))
    )
    (net (code "137") (name "Net-(S1-P)") (class "Default")
      (node (ref "J1") (pin "3") (pinfunction "3_3") (pintype "passive"))
      (node (ref "S1") (pin "2") (pinfunction "P_2") (pintype "passive"))
    )
    (net (code "138") (name "Net-(U$2-Pad3V3_LO)") (class "Default")
      (node (ref "U$2") (pin "3V3_LO") (pinfunction "3V3_LO_3V3_LO") (pintype "bidirectional"))
      (node (ref "U$2") (pin "AREF") (pinfunction "AREF_AREF") (pintype "bidirectional"))
    )
    (net (code "139") (name "VCC") (class "Default")
      (node (ref "B1") (pin "HV") (pinfunction "HV_HV") (pintype "power_in"))
      (node (ref "B2") (pin "HV") (pinfunction "HV_HV") (pintype "power_in"))
      (node (ref "B3") (pin "HV") (pinfunction "HV_HV") (pintype "power_in"))
      (node (ref "B4") (pin "HV") (pinfunction "HV_HV") (pintype "power_in"))
      (node (ref "B5") (pin "HV") (pinfunction "HV_HV") (pintype "power_in"))
      (node (ref "B6") (pin "HV") (pinfunction "HV_HV") (pintype "power_in"))
      (node (ref "C1") (pin "2") (pinfunction "2_2") (pintype "passive"))
      (node (ref "C10") (pin "+") (pinfunction "+_+") (pintype "passive"))
      (node (ref "C11") (pin "1") (pinfunction "1_1") (pintype "passive"))
      (node (ref "C12") (pin "2") (pinfunction "2_2") (pintype "passive"))
      (node (ref "C13") (pin "2") (pinfunction "2_2") (pintype "passive"))
      (node (ref "C2") (pin "2") (pinfunction "2_2") (pintype "passive"))
      (node (ref "C3") (pin "2") (pinfunction "2_2") (pintype "passive"))
      (node (ref "C4") (pin "2") (pinfunction "2_2") (pintype "passive"))
      (node (ref "C5") (pin "2") (pinfunction "2_2") (pintype "passive"))
      (node (ref "C6") (pin "2") (pinfunction "2_2") (pintype "passive"))
      (node (ref "C7") (pin "2") (pinfunction "2_2") (pintype "passive"))
      (node (ref "C8") (pin "2") (pinfunction "2_2") (pintype "passive"))
      (node (ref "IC1") (pin "14") (pinfunction "VCC_14") (pintype "power_in"))
      (node (ref "IC11") (pin "14") (pinfunction "VCC_14") (pintype "power_in"))
      (node (ref "IC13") (pin "14") (pinfunction "VCC_14") (pintype "power_in"))
      (node (ref "IC2") (pin "20") (pinfunction "VCC_20") (pintype "power_in"))
      (node (ref "IC3") (pin "14") (pinfunction "VCC_14") (pintype "power_in"))
      (node (ref "IC4") (pin "20") (pinfunction "VCC_20") (pintype "power_in"))
      (node (ref "IC5") (pin "12") (pinfunction "D_12") (pintype "input"))
      (node (ref "IC5") (pin "14") (pinfunction "VCC_14") (pintype "power_in"))
      (node (ref "IC5") (pin "2") (pinfunction "D_2") (pintype "input"))
      (node (ref "IC6") (pin "16") (pinfunction "VCC_16") (pintype "power_in"))
      (node (ref "IC7") (pin "16") (pinfunction "VCC_16") (pintype "power_in"))
      (node (ref "IC8") (pin "28") (pinfunction "VCC_28") (pintype "power_in"))
      (node (ref "IC9") (pin "3") (pinfunction "VO_3") (pintype "passive"))
      (node (ref "J2") (pin "2") (pinfunction "2_2") (pintype "passive"))
      (node (ref "J3") (pin "2") (pinfunction "2_2") (pintype "passive"))
      (node (ref "R7") (pin "1") (pinfunction "1_1") (pintype "passive"))
      (node (ref "U$2") (pin "VIN") (pinfunction "VIN_VIN") (pintype "bidirectional"))
    )
    (net (code "140") (name "VCC{slash}2") (class "Default")
      (node (ref "B1") (pin "LV") (pinfunction "LV_LV") (pintype "power_in"))
      (node (ref "B2") (pin "LV") (pinfunction "LV_LV") (pintype "power_in"))
      (node (ref "B3") (pin "LV") (pinfunction "LV_LV") (pintype "power_in"))
      (node (ref "B4") (pin "LV") (pinfunction "LV_LV") (pintype "power_in"))
      (node (ref "B5") (pin "LV") (pinfunction "LV_LV") (pintype "power_in"))
      (node (ref "B6") (pin "LV") (pinfunction "LV_LV") (pintype "power_in"))
      (node (ref "U$2") (pin "3V3_2") (pinfunction "3V3_2_3V3_2") (pintype "bidirectional"))
    )
    (net (code "141") (name "unconnected-(IC1C-O-Pad8)") (class "Default")
      (node (ref "IC1") (pin "8") (pinfunction "O_8") (pintype "output"))
    )
    (net (code "142") (name "unconnected-(IC5A-Q-Pad5)") (class "Default")
      (node (ref "IC5") (pin "5") (pinfunction "Q_5") (pintype "output"))
    )
    (net (code "143") (name "unconnected-(IC5B-Q-Pad9)") (class "Default")
      (node (ref "IC5") (pin "9") (pinfunction "Q_9") (pintype "output"))
    )
    (net (code "144") (name "unconnected-(IC6A-Y1-Pad5)") (class "Default")
      (node (ref "IC6") (pin "5") (pinfunction "Y1_5") (pintype "output"))
    )
    (net (code "145") (name "unconnected-(IC6A-Y2-Pad6)") (class "Default")
      (node (ref "IC6") (pin "6") (pinfunction "Y2_6") (pintype "output"))
    )
    (net (code "146") (name "unconnected-(IC6A-Y3-Pad7)") (class "Default")
      (node (ref "IC6") (pin "7") (pinfunction "Y3_7") (pintype "output"))
    )
    (net (code "147") (name "unconnected-(IC6B-Y1-Pad11)") (class "Default")
      (node (ref "IC6") (pin "11") (pinfunction "Y1_11") (pintype "output"))
    )
    (net (code "148") (name "unconnected-(IC6B-Y2-Pad10)") (class "Default")
      (node (ref "IC6") (pin "10") (pinfunction "Y2_10") (pintype "output"))
    )
    (net (code "149") (name "unconnected-(IC6B-Y3-Pad9)") (class "Default")
      (node (ref "IC6") (pin "9") (pinfunction "Y3_9") (pintype "output"))
    )
    (net (code "150") (name "unconnected-(IC13C-O-Pad8)") (class "Default")
      (node (ref "IC13") (pin "8") (pinfunction "O_8") (pintype "output"))
    )
    (net (code "151") (name "unconnected-(IC13D-O-Pad11)") (class "Default")
      (node (ref "IC13") (pin "11") (pinfunction "O_11") (pintype "output"))
    )
    (net (code "152") (name "unconnected-(J3-Pad4)") (class "Default")
      (node (ref "J3") (pin "4") (pinfunction "4_4") (pintype "passive"))
    )
    (net (code "153") (name "unconnected-(J3-Pad6)") (class "Default")
      (node (ref "J3") (pin "6") (pinfunction "6_6") (pintype "passive"))
    )
    (net (code "154") (name "unconnected-(J3-Pad8)") (class "Default")
      (node (ref "J3") (pin "8") (pinfunction "8_8") (pintype "passive"))
    )
    (net (code "155") (name "unconnected-(S1-O-Pad1)") (class "Default")
      (node (ref "S1") (pin "1") (pinfunction "O_1") (pintype "passive"))
    )
    (net (code "156") (name "unconnected-(U$1-CAS*-PadP$3)") (class "Default")
      (node (ref "U$1") (pin "P$3") (pinfunction "CAS*_P$3") (pintype "bidirectional"))
    )
    (net (code "157") (name "unconnected-(U$1-IN*-PadP$19)") (class "Default")
      (node (ref "U$1") (pin "P$19") (pinfunction "IN*_P$19") (pintype "bidirectional"))
    )
    (net (code "158") (name "unconnected-(U$1-INTAK*-PadP$14)") (class "Default")
      (node (ref "U$1") (pin "P$14") (pinfunction "INTAK*_P$14") (pintype "bidirectional"))
    )
    (net (code "159") (name "unconnected-(U$1-MUX-PadP$16)") (class "Default")
      (node (ref "U$1") (pin "P$16") (pinfunction "MUX_P$16") (pintype "bidirectional"))
    )
    (net (code "160") (name "unconnected-(U$1-NC-PadP$39)") (class "Default")
      (node (ref "U$1") (pin "P$39") (pinfunction "NC_P$39") (pintype "bidirectional"))
    )
    (net (code "161") (name "unconnected-(U$1-OUT*-PadP$12)") (class "Default")
      (node (ref "U$1") (pin "P$12") (pinfunction "OUT*_P$12") (pintype "bidirectional"))
    )
    (net (code "162") (name "unconnected-(U$1-SYSRES*-PadP$2)") (class "Default")
      (node (ref "U$1") (pin "P$2") (pinfunction "SYSRES*_P$2") (pintype "bidirectional"))
    )
    (net (code "163") (name "unconnected-(U$1-TEST*-PadP$23)") (class "Default")
      (node (ref "U$1") (pin "P$23") (pinfunction "TEST*_P$23") (pintype "bidirectional"))
    )
    (net (code "164") (name "unconnected-(U$2-A21{slash}DAC0-Pad21{slash}DAC0)") (class "Default")
      (node (ref "U$2") (pin "21/DAC0") (pinfunction "A21/DAC0_21/DAC0") (pintype "bidirectional"))
    )
    (net (code "165") (name "unconnected-(U$2-Pad0{slash}RX)") (class "Default")
      (node (ref "U$2") (pin "0/RX") (pinfunction "0/RX_0/RX") (pintype "bidirectional"))
    )
    (net (code "166") (name "unconnected-(U$2-Pad1{slash}TX)") (class "Default")
      (node (ref "U$2") (pin "1/TX") (pinfunction "1/TX_1/TX") (pintype "bidirectional"))
    )
    (net (code "167") (name "unconnected-(U$2-Pad3V3)") (class "Default")
      (node (ref "U$2") (pin "3V3") (pinfunction "3V3_3V3") (pintype "bidirectional"))
    )
    (net (code "168") (name "unconnected-(U$2-Pad14{slash}A0)") (class "Default")
      (node (ref "U$2") (pin "14/A0") (pinfunction "14/A0_14/A0") (pintype "bidirectional"))
    )
    (net (code "169") (name "unconnected-(U$2-Pad16{slash}A2)") (class "Default")
      (node (ref "U$2") (pin "16/A2") (pinfunction "16/A2_16/A2") (pintype "bidirectional"))
    )
    (net (code "170") (name "unconnected-(U$2-Pad17{slash}A3)") (class "Default")
      (node (ref "U$2") (pin "17/A3") (pinfunction "17/A3_17/A3") (pintype "bidirectional"))
    )
    (net (code "171") (name "unconnected-(U$2-Pad18{slash}A4{slash}SDA)") (class "Default")
      (node (ref "U$2") (pin "18/A4/SDA") (pinfunction "18/A4/SDA_18/A4/SDA") (pintype "bidirectional"))
    )
    (net (code "172") (name "unconnected-(U$2-Pad19{slash}A5{slash}SCL)") (class "Default")
      (node (ref "U$2") (pin "19/A5/SCL") (pinfunction "19/A5/SCL_19/A5/SCL") (pintype "bidirectional"))
    )
    (net (code "173") (name "unconnected-(U$2-Pad20{slash}A6)") (class "Default")
      (node (ref "U$2") (pin "20/A6") (pinfunction "20/A6_20/A6") (pintype "bidirectional"))
    )
    (net (code "174") (name "unconnected-(U$2-Pad21{slash}A7)") (class "Default")
      (node (ref "U$2") (pin "21/A7") (pinfunction "21/A7_21/A7") (pintype "bidirectional"))
    )
    (net (code "175") (name "unconnected-(U$2-Pad24)") (class "Default")
      (node (ref "U$2") (pin "24") (pinfunction "24_24") (pintype "bidirectional"))
    )
    (net (code "176") (name "unconnected-(U$2-PadA10)") (class "Default")
      (node (ref "U$2") (pin "A10") (pinfunction "A10_A10") (pintype "bidirectional"))
    )
    (net (code "177") (name "unconnected-(U$2-PadA11)") (class "Default")
      (node (ref "U$2") (pin "A11") (pinfunction "A11_A11") (pintype "bidirectional"))
    )
    (net (code "178") (name "unconnected-(U$2-PadA22{slash}DAC1)") (class "Default")
      (node (ref "U$2") (pin "A22/DAC1") (pinfunction "A22/DAC1_A22/DAC1") (pintype "bidirectional"))
    )
    (net (code "179") (name "unconnected-(U$2-PadPROG)") (class "Default")
      (node (ref "U$2") (pin "PROG") (pinfunction "PROG_PROG") (pintype "bidirectional"))
    )
    (net (code "180") (name "unconnected-(U$2-PadRESET)") (class "Default")
      (node (ref "U$2") (pin "RESET") (pinfunction "RESET_RESET") (pintype "bidirectional"))
    )
    (net (code "181") (name "unconnected-(U$2-PadU5V)") (class "Default")
      (node (ref "U$2") (pin "U5V") (pinfunction "U5V_U5V") (pintype "bidirectional"))
    )
    (net (code "182") (name "unconnected-(U$2-PadUD+)") (class "Default")
      (node (ref "U$2") (pin "UD+") (pinfunction "UD+_UD+") (pintype "bidirectional"))
    )
    (net (code "183") (name "unconnected-(U$2-PadUD-)") (class "Default")
      (node (ref "U$2") (pin "UD-") (pinfunction "UD-_UD-") (pintype "bidirectional"))
    )
    (net (code "184") (name "unconnected-(U$2-PadVBAT)") (class "Default")
      (node (ref "U$2") (pin "VBAT") (pinfunction "VBAT_VBAT") (pintype "bidirectional"))
    )
    (net (code "185") (name "unconnected-(U$2-PadVUSB)") (class "Default")
      (node (ref "U$2") (pin "VUSB") (pinfunction "VUSB_VUSB") (pintype "bidirectional"))
    )
  )
)
